# AdapterBoard.net
KiCad netlist of a schematic drawn in Altium Designer
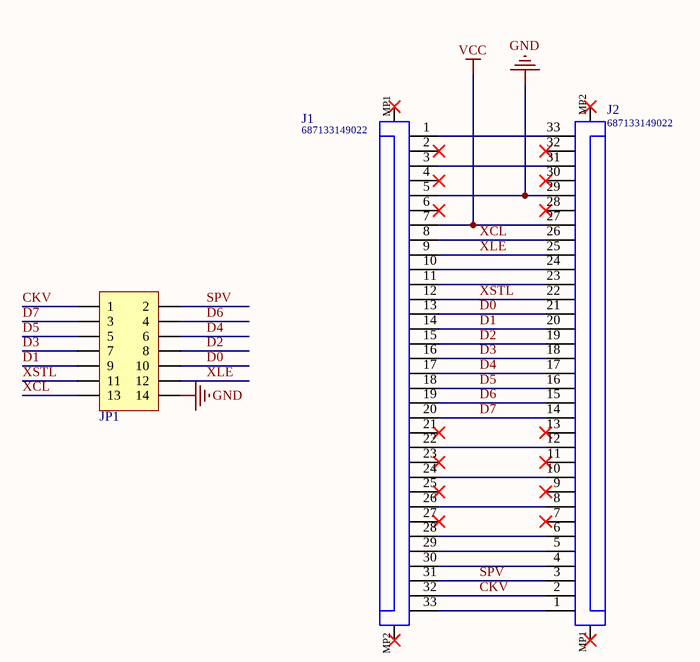
[diagram p0: AdapterBoard.SchDoc]

(export (version "E")
  (design (tool "Eeschema 10.0.6"))
  (components
    (comp (ref "J1")
      (value "687133149022")
      (footprint "687133149022")
      (description "SMT ZIF Connectors Hinge Type WR-FPC, Horizontal, Bottom Contact, pitch 0.5 mm, 33 pins")
      (fields (field (name "MANUFACTURER") "Wurth Elektronik") (field (name "PUBLISHER") "WurthElektronik"))
      (libsource (lib "Altium Content Vault") (part "WE-6871331XXX22-33"))
    )
    (comp (ref "J2")
      (value "687133149022")
      (footprint "687133149022")
      (description "SMT ZIF Connectors Hinge Type WR-FPC, Horizontal, Bottom Contact, pitch 0.5 mm, 33 pins")
      (fields (field (name "MANUFACTURER") "Wurth Elektronik") (field (name "PUBLISHER") "WurthElektronik"))
      (libsource (lib "Altium Content Vault") (part "WE-6871331XXX22-33"))
    )
    (comp (ref "JP1")
      (value "Header 2X7")
      (footprint "HDR2.54-LI-2x7P")
      (description "7*2P接插件")
      (libsource (lib "5.5 - 接插件-脚距2.54 (100mil) ") (part "Header 7X2"))
    )
  )
  (nets
    (net (code "1") (name "/CKV") (class "Default")
      (node (ref "J1") (pin "32") (pinfunction "32_32") (pintype "passive"))
      (node (ref "J2") (pin "2") (pinfunction "2_2") (pintype "passive"))
      (node (ref "JP1") (pin "1") (pinfunction "1_1") (pintype "passive"))
    )
    (net (code "2") (name "/D0") (class "Default")
      (node (ref "J1") (pin "13") (pinfunction "13_13") (pintype "passive"))
      (node (ref "J2") (pin "21") (pinfunction "21_21") (pintype "passive"))
      (node (ref "JP1") (pin "10") (pinfunction "10_10") (pintype "passive"))
    )
    (net (code "3") (name "/D1") (class "Default")
      (node (ref "J1") (pin "14") (pinfunction "14_14") (pintype "passive"))
      (node (ref "J2") (pin "20") (pinfunction "20_20") (pintype "passive"))
      (node (ref "JP1") (pin "9") (pinfunction "9_9") (pintype "passive"))
    )
    (net (code "4") (name "/D2") (class "Default")
      (node (ref "J1") (pin "15") (pinfunction "15_15") (pintype "passive"))
      (node (ref "J2") (pin "19") (pinfunction "19_19") (pintype "passive"))
      (node (ref "JP1") (pin "8") (pinfunction "8_8") (pintype "passive"))
    )
    (net (code "5") (name "/D3") (class "Default")
      (node (ref "J1") (pin "16") (pinfunction "16_16") (pintype "passive"))
      (node (ref "J2") (pin "18") (pinfunction "18_18") (pintype "passive"))
      (node (ref "JP1") (pin "7") (pinfunction "7_7") (pintype "passive"))
    )
    (net (code "6") (name "/D4") (class "Default")
      (node (ref "J1") (pin "17") (pinfunction "17_17") (pintype "passive"))
      (node (ref "J2") (pin "17") (pinfunction "17_17") (pintype "passive"))
      (node (ref "JP1") (pin "6") (pinfunction "6_6") (pintype "passive"))
    )
    (net (code "7") (name "/D5") (class "Default")
      (node (ref "J1") (pin "18") (pinfunction "18_18") (pintype "passive"))
      (node (ref "J2") (pin "16") (pinfunction "16_16") (pintype "passive"))
      (node (ref "JP1") (pin "5") (pinfunction "5_5") (pintype "passive"))
    )
    (net (code "8") (name "/D6") (class "Default")
      (node (ref "J1") (pin "19") (pinfunction "19_19") (pintype "passive"))
      (node (ref "J2") (pin "15") (pinfunction "15_15") (pintype "passive"))
      (node (ref "JP1") (pin "4") (pinfunction "4_4") (pintype "passive"))
    )
    (net (code "9") (name "/D7") (class "Default")
      (node (ref "J1") (pin "20") (pinfunction "20_20") (pintype "passive"))
      (node (ref "J2") (pin "14") (pinfunction "14_14") (pintype "passive"))
      (node (ref "JP1") (pin "3") (pinfunction "3_3") (pintype "passive"))
    )
    (net (code "10") (name "/SPV") (class "Default")
      (node (ref "J1") (pin "31") (pinfunction "31_31") (pintype "passive"))
      (node (ref "J2") (pin "3") (pinfunction "3_3") (pintype "passive"))
      (node (ref "JP1") (pin "2") (pinfunction "2_2") (pintype "passive"))
    )
    (net (code "11") (name "/XCL") (class "Default")
      (node (ref "J1") (pin "8") (pinfunction "8_8") (pintype "passive"))
      (node (ref "J2") (pin "26") (pinfunction "26_26") (pintype "passive"))
      (node (ref "JP1") (pin "13") (pinfunction "13_13") (pintype "passive"))
    )
    (net (code "12") (name "/XLE") (class "Default")
      (node (ref "J1") (pin "9") (pinfunction "9_9") (pintype "passive"))
      (node (ref "J2") (pin "25") (pinfunction "25_25") (pintype "passive"))
      (node (ref "JP1") (pin "12") (pinfunction "12_12") (pintype "passive"))
    )
    (net (code "13") (name "/XSTL") (class "Default")
      (node (ref "J1") (pin "12") (pinfunction "12_12") (pintype "passive"))
      (node (ref "J2") (pin "22") (pinfunction "22_22") (pintype "passive"))
      (node (ref "JP1") (pin "11") (pinfunction "11_11") (pintype "passive"))
    )
    (net (code "14") (name "GND") (class "Default")
      (node (ref "J1") (pin "5") (pinfunction "5_5") (pintype "passive"))
      (node (ref "J2") (pin "29") (pinfunction "29_29") (pintype "passive"))
      (node (ref "JP1") (pin "14") (pinfunction "14_14") (pintype "passive"))
    )
    (net (code "15") (name "Net-(J1-Pad1)") (class "Default")
      (node (ref "J1") (pin "1") (pinfunction "1_1") (pintype "passive"))
      (node (ref "J2") (pin "33") (pinfunction "33_33") (pintype "passive"))
    )
    (net (code "16") (name "Net-(J1-Pad3)") (class "Default")
      (node (ref "J1") (pin "3") (pinfunction "3_3") (pintype "passive"))
      (node (ref "J2") (pin "31") (pinfunction "31_31") (pintype "passive"))
    )
    (net (code "17") (name "Net-(J1-Pad10)") (class "Default")
      (node (ref "J1") (pin "10") (pinfunction "10_10") (pintype "passive"))
      (node (ref "J2") (pin "24") (pinfunction "24_24") (pintype "passive"))
    )
    (net (code "18") (name "Net-(J1-Pad11)") (class "Default")
      (node (ref "J1") (pin "11") (pinfunction "11_11") (pintype "passive"))
      (node (ref "J2") (pin "23") (pinfunction "23_23") (pintype "passive"))
    )
    (net (code "19") (name "Net-(J1-Pad22)") (class "Default")
      (node (ref "J1") (pin "22") (pinfunction "22_22") (pintype "passive"))
      (node (ref "J2") (pin "12") (pinfunction "12_12") (pintype "passive"))
    )
    (net (code "20") (name "Net-(J1-Pad24)") (class "Default")
      (node (ref "J1") (pin "24") (pinfunction "24_24") (pintype "passive"))
      (node (ref "J2") (pin "10") (pinfunction "10_10") (pintype "passive"))
    )
    (net (code "21") (name "Net-(J1-Pad26)") (class "Default")
      (node (ref "J1") (pin "26") (pinfunction "26_26") (pintype "passive"))
      (node (ref "J2") (pin "8") (pinfunction "8_8") (pintype "passive"))
    )
    (net (code "22") (name "Net-(J1-Pad28)") (class "Default")
      (node (ref "J1") (pin "28") (pinfunction "28_28") (pintype "passive"))
      (node (ref "J2") (pin "6") (pinfunction "6_6") (pintype "passive"))
    )
    (net (code "23") (name "Net-(J1-Pad29)") (class "Default")
      (node (ref "J1") (pin "29") (pinfunction "29_29") (pintype "passive"))
      (node (ref "J2") (pin "5") (pinfunction "5_5") (pintype "passive"))
    )
    (net (code "24") (name "Net-(J1-Pad30)") (class "Default")
      (node (ref "J1") (pin "30") (pinfunction "30_30") (pintype "passive"))
      (node (ref "J2") (pin "4") (pinfunction "4_4") (pintype "passive"))
    )
    (net (code "25") (name "Net-(J1-Pad33)") (class "Default")
      (node (ref "J1") (pin "33") (pinfunction "33_33") (pintype "passive"))
      (node (ref "J2") (pin "1") (pinfunction "1_1") (pintype "passive"))
    )
    (net (code "26") (name "VCC") (class "Default")
      (node (ref "J1") (pin "7") (pinfunction "7_7") (pintype "passive"))
      (node (ref "J2") (pin "27") (pinfunction "27_27") (pintype "passive"))
    )
    (net (code "27") (name "unconnected-(J1-Pad2)") (class "Default")
      (node (ref "J1") (pin "2") (pinfunction "2_2") (pintype "passive+no_connect"))
    )
    (net (code "28") (name "unconnected-(J1-Pad4)") (class "Default")
      (node (ref "J1") (pin "4") (pinfunction "4_4") (pintype "passive+no_connect"))
    )
    (net (code "29") (name "unconnected-(J1-Pad6)") (class "Default")
      (node (ref "J1") (pin "6") (pinfunction "6_6") (pintype "passive+no_connect"))
    )
    (net (code "30") (name "unconnected-(J1-Pad21)") (class "Default")
      (node (ref "J1") (pin "21") (pinfunction "21_21") (pintype "passive+no_connect"))
    )
    (net (code "31") (name "unconnected-(J1-Pad23)") (class "Default")
      (node (ref "J1") (pin "23") (pinfunction "23_23") (pintype "passive+no_connect"))
    )
    (net (code "32") (name "unconnected-(J1-Pad25)") (class "Default")
      (node (ref "J1") (pin "25") (pinfunction "25_25") (pintype "passive+no_connect"))
    )
    (net (code "33") (name "unconnected-(J1-Pad27)") (class "Default")
      (node (ref "J1") (pin "27") (pinfunction "27_27") (pintype "passive+no_connect"))
    )
    (net (code "34") (name "unconnected-(J1-PadMP1)") (class "Default")
      (node (ref "J1") (pin "MP1") (pinfunction "MP1_MP1") (pintype "passive+no_connect"))
    )
    (net (code "35") (name "unconnected-(J1-PadMP2)") (class "Default")
      (node (ref "J1") (pin "MP2") (pinfunction "MP2_MP2") (pintype "passive+no_connect"))
    )
    (net (code "36") (name "unconnected-(J2-Pad7)") (class "Default")
      (node (ref "J2") (pin "7") (pinfunction "7_7") (pintype "passive+no_connect"))
    )
    (net (code "37") (name "unconnected-(J2-Pad9)") (class "Default")
      (node (ref "J2") (pin "9") (pinfunction "9_9") (pintype "passive+no_connect"))
    )
    (net (code "38") (name "unconnected-(J2-Pad11)") (class "Default")
      (node (ref "J2") (pin "11") (pinfunction "11_11") (pintype "passive+no_connect"))
    )
    (net (code "39") (name "unconnected-(J2-Pad13)") (class "Default")
      (node (ref "J2") (pin "13") (pinfunction "13_13") (pintype "passive+no_connect"))
    )
    (net (code "40") (name "unconnected-(J2-Pad28)") (class "Default")
      (node (ref "J2") (pin "28") (pinfunction "28_28") (pintype "passive+no_connect"))
    )
    (net (code "41") (name "unconnected-(J2-Pad30)") (class "Default")
      (node (ref "J2") (pin "30") (pinfunction "30_30") (pintype "passive+no_connect"))
    )
    (net (code "42") (name "unconnected-(J2-Pad32)") (class "Default")
      (node (ref "J2") (pin "32") (pinfunction "32_32") (pintype "passive+no_connect"))
    )
    (net (code "43") (name "unconnected-(J2-PadMP1)") (class "Default")
      (node (ref "J2") (pin "MP1") (pinfunction "MP1_MP1") (pintype "passive+no_connect"))
    )
    (net (code "44") (name "unconnected-(J2-PadMP2)") (class "Default")
      (node (ref "J2") (pin "MP2") (pinfunction "MP2_MP2") (pintype "passive+no_connect"))
    )
  )
)
